# Headphone-Amplifier-ClassAB-alt3.net
KiCad netlist of a schematic drawn in EAGLE
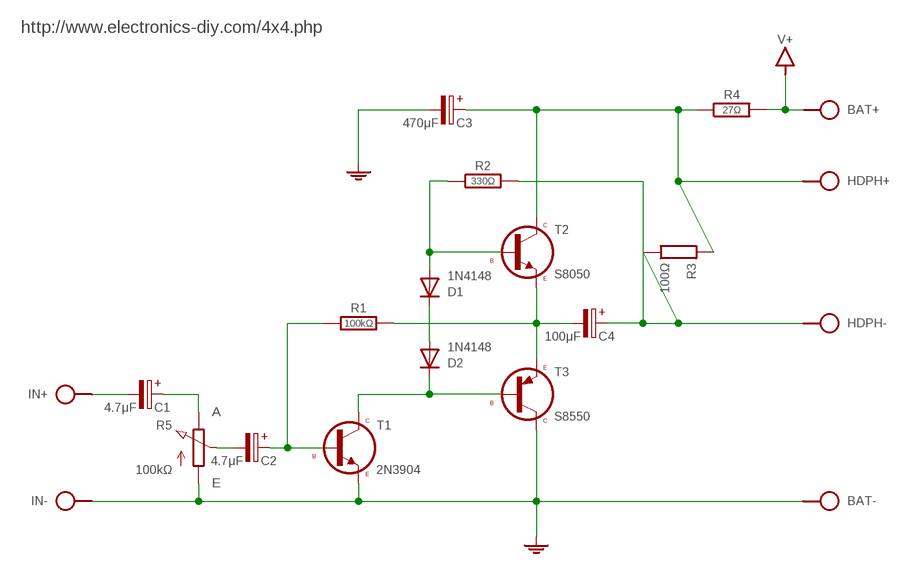
[diagram p0: schematic, sheet 1]

(export (version "E")
  (design (tool "Eeschema 10.0.6"))
  (components
    (comp (ref "BAT")
      (value "SPAD+-+-")
      (footprint "eagle-import:SPAD+-")
      (libsource (lib "eagle-import") (part "SPAD+-+-"))
    )
    (comp (ref "C1")
      (value "4.7μF")
      (footprint "eagle-import:E2,5-3")
      (libsource (lib "eagle-import") (part "CPOL-HE2,5-3"))
    )
    (comp (ref "C2")
      (value "4.7μF")
      (footprint "eagle-import:E2,5-3")
      (libsource (lib "eagle-import") (part "CPOL-HE2,5-3"))
    )
    (comp (ref "C3")
      (value "470μF")
      (footprint "eagle-import:E2,5-5_V")
      (libsource (lib "eagle-import") (part "CPOL-HE2,5-5/V"))
    )
    (comp (ref "C4")
      (value "100μF")
      (footprint "eagle-import:E5-4")
      (libsource (lib "eagle-import") (part "CPOL-HE5-4"))
    )
    (comp (ref "D1")
      (value "1N4148")
      (footprint "eagle-import:DO34-5-V")
      (libsource (lib "eagle-import") (part "DIODE34-5-V"))
    )
    (comp (ref "D2")
      (value "1N4148")
      (footprint "eagle-import:DO34-5V")
      (libsource (lib "eagle-import") (part "DIODE34-5V"))
    )
    (comp (ref "HDPH")
      (value "SPAD+--+")
      (footprint "eagle-import:SPAD-+")
      (libsource (lib "eagle-import") (part "SPAD+--+"))
    )
    (comp (ref "IN")
      (value "SPAD+--+")
      (footprint "eagle-import:SPAD-+")
      (libsource (lib "eagle-import") (part "SPAD+--+"))
    )
    (comp (ref "R1")
      (value "100kΩ")
      (footprint "eagle-import:0204_10")
      (libsource (lib "eagle-import") (part "R-H0204/10"))
    )
    (comp (ref "R2")
      (value "330Ω")
      (footprint "eagle-import:0204_10")
      (libsource (lib "eagle-import") (part "R-H0204/10"))
    )
    (comp (ref "R3")
      (value "100Ω")
      (footprint "eagle-import:0204_10")
      (libsource (lib "eagle-import") (part "R0204/10"))
    )
    (comp (ref "R4")
      (value "27Ω")
      (footprint "eagle-import:0204_10")
      (libsource (lib "eagle-import") (part "R-H0204/10"))
    )
    (comp (ref "R5")
      (value "100kΩ")
      (footprint "eagle-import:CONN-3P")
      (libsource (lib "eagle-import") (part "POT-3P"))
    )
    (comp (ref "T1")
      (value "2N3904")
      (footprint "eagle-import:TO92-EBC")
      (libsource (lib "eagle-import") (part "2N3904EBC"))
    )
    (comp (ref "T2")
      (value "S8050")
      (footprint "eagle-import:TO92-EBC")
      (libsource (lib "eagle-import") (part "S8050-TO92"))
    )
    (comp (ref "T3")
      (value "S8550")
      (footprint "eagle-import:TO92-EBC")
      (libsource (lib "eagle-import") (part "S8550-TO92"))
    )
  )
  (nets
    (net (code "1") (name "GND") (class "Default")
      (node (ref "BAT") (pin "1") (pinfunction "P$1_1") (pintype "passive"))
      (node (ref "C3") (pin "-") (pinfunction "-_-") (pintype "passive"))
      (node (ref "IN") (pin "1") (pinfunction "P$1_1") (pintype "passive"))
      (node (ref "R5") (pin "1") (pinfunction "A_1") (pintype "passive"))
      (node (ref "T1") (pin "E") (pinfunction "E_E") (pintype "passive"))
      (node (ref "T3") (pin "C") (pinfunction "C_C") (pintype "passive"))
    )
    (net (code "2") (name "Net-(C2-Pad+)") (class "Default")
      (node (ref "C2") (pin "+") (pinfunction "+_+") (pintype "passive"))
      (node (ref "R1") (pin "1") (pinfunction "1_1") (pintype "passive"))
      (node (ref "T1") (pin "B") (pinfunction "B_B") (pintype "passive"))
    )
    (net (code "3") (name "Net-(C4-Pad-)") (class "Default")
      (node (ref "C4") (pin "-") (pinfunction "-_-") (pintype "passive"))
      (node (ref "R1") (pin "2") (pinfunction "2_2") (pintype "passive"))
      (node (ref "T2") (pin "E") (pinfunction "E_E") (pintype "passive"))
      (node (ref "T3") (pin "E") (pinfunction "E_E") (pintype "passive"))
    )
    (net (code "4") (name "Net-(D1-PadA)") (class "Default")
      (node (ref "D1") (pin "A") (pinfunction "A_A") (pintype "passive"))
      (node (ref "R2") (pin "1") (pinfunction "1_1") (pintype "passive"))
      (node (ref "T2") (pin "B") (pinfunction "B_B") (pintype "passive"))
    )
    (net (code "5") (name "Net-(D1-PadC)") (class "Default")
      (node (ref "D1") (pin "C") (pinfunction "C_C") (pintype "passive"))
      (node (ref "D2") (pin "A") (pinfunction "A_A") (pintype "passive"))
    )
    (net (code "6") (name "Net-(D2-PadC)") (class "Default")
      (node (ref "D2") (pin "C") (pinfunction "C_C") (pintype "passive"))
      (node (ref "T1") (pin "C") (pinfunction "C_C") (pintype "passive"))
      (node (ref "T3") (pin "B") (pinfunction "B_B") (pintype "passive"))
    )
    (net (code "7") (name "Net-(HDPHA-P$1)") (class "Default")
      (node (ref "C3") (pin "+") (pinfunction "+_+") (pintype "passive"))
      (node (ref "HDPH") (pin "2") (pinfunction "P$1_2") (pintype "passive"))
      (node (ref "R3") (pin "1") (pinfunction "2_1") (pintype "passive"))
      (node (ref "R4") (pin "1") (pinfunction "1_1") (pintype "passive"))
      (node (ref "T2") (pin "C") (pinfunction "C_C") (pintype "passive"))
    )
    (net (code "8") (name "Net-(HDPHB-P$1)") (class "Default")
      (node (ref "C4") (pin "+") (pinfunction "+_+") (pintype "passive"))
      (node (ref "HDPH") (pin "1") (pinfunction "P$1_1") (pintype "passive"))
      (node (ref "R2") (pin "2") (pinfunction "2_2") (pintype "passive"))
      (node (ref "R3") (pin "2") (pinfunction "1_2") (pintype "passive"))
    )
    (net (code "9") (name "Net-(INA-P$1)") (class "Default")
      (node (ref "C1") (pin "-") (pinfunction "-_-") (pintype "passive"))
      (node (ref "IN") (pin "2") (pinfunction "P$1_2") (pintype "passive"))
    )
    (net (code "10") (name "Net-(R5-E)") (class "Default")
      (node (ref "C1") (pin "+") (pinfunction "+_+") (pintype "passive"))
      (node (ref "R5") (pin "3") (pinfunction "E_3") (pintype "passive"))
    )
    (net (code "11") (name "Net-(R5-S)") (class "Default")
      (node (ref "C2") (pin "-") (pinfunction "-_-") (pintype "passive"))
      (node (ref "R5") (pin "2") (pinfunction "S_2") (pintype "passive"))
    )
    (net (code "12") (name "V+") (class "Default")
      (node (ref "BAT") (pin "2") (pinfunction "P$1_2") (pintype "passive"))
      (node (ref "R4") (pin "2") (pinfunction "2_2") (pintype "passive"))
    )
  )
)
